# IFM_DuberFilter_ThroughHole_PCB.net
KiCad netlist of a schematic drawn in EAGLE
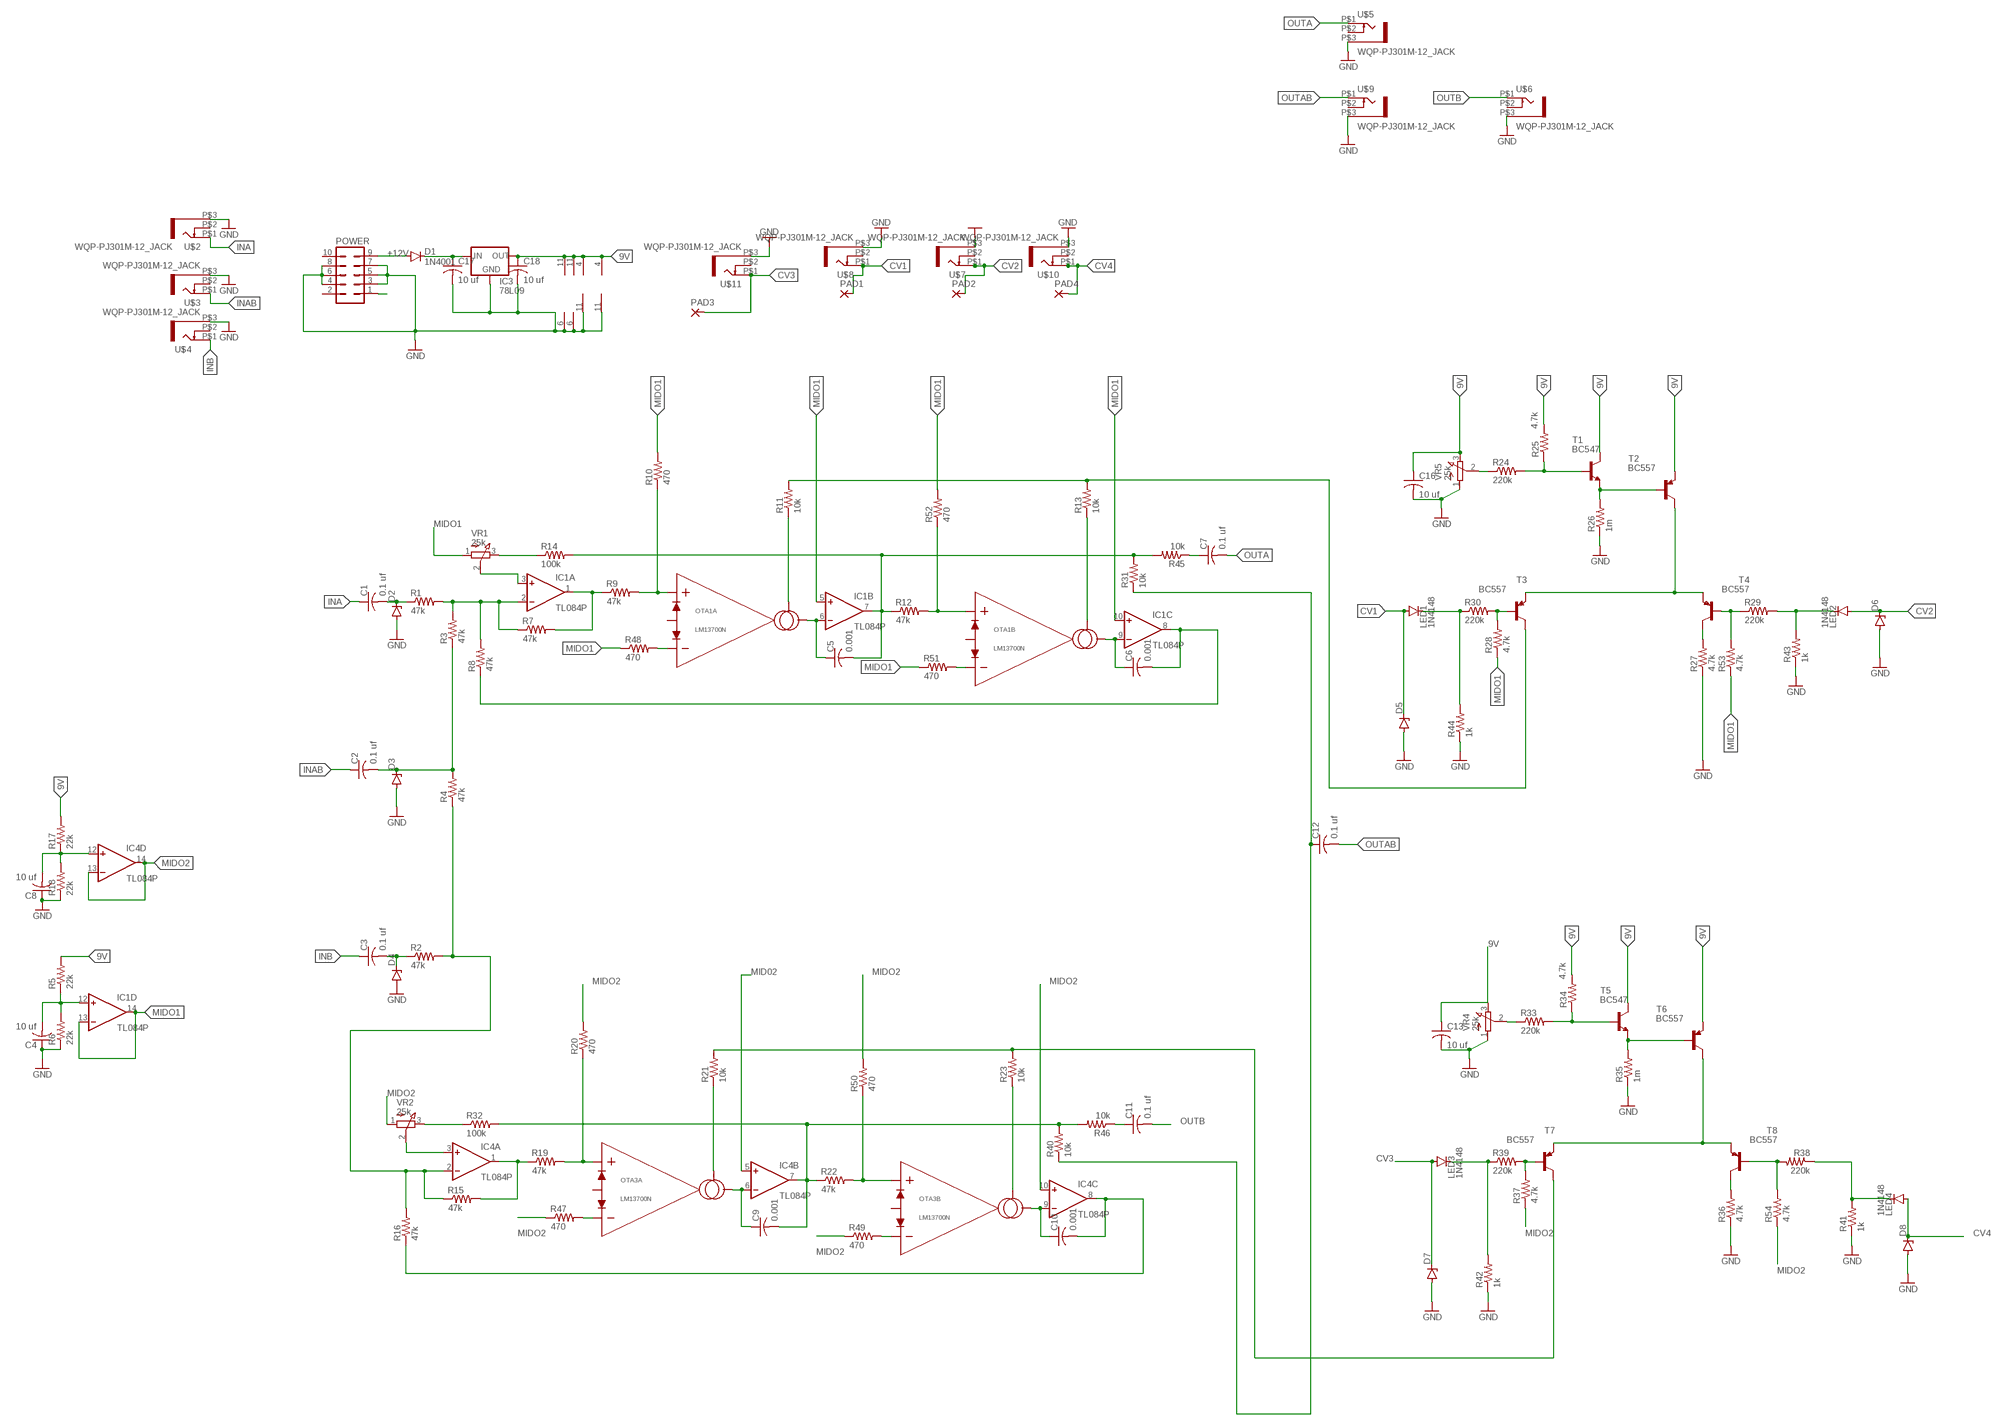
[diagram p0: schematic, sheet 1]

(export (version "E")
  (design (tool "Eeschema 10.0.6"))
  (components
    (comp (ref "C1")
      (value "0.1 uf")
      (footprint "eagle-import:C050-030X075")
      (libsource (lib "eagle-import") (part "C-US050-030X075"))
    )
    (comp (ref "C2")
      (value "0.1 uf")
      (footprint "eagle-import:C050-030X075")
      (libsource (lib "eagle-import") (part "C-US050-030X075"))
    )
    (comp (ref "C3")
      (value "0.1 uf")
      (footprint "eagle-import:C050-030X075")
      (libsource (lib "eagle-import") (part "C-US050-030X075"))
    )
    (comp (ref "C4")
      (value "10 uf")
      (footprint "eagle-import:C050-030X075")
      (libsource (lib "eagle-import") (part "C-US050-030X075"))
    )
    (comp (ref "C5")
      (value "0.001")
      (footprint "eagle-import:C050-030X075")
      (libsource (lib "eagle-import") (part "C-US050-030X075"))
    )
    (comp (ref "C6")
      (value "0.001")
      (footprint "eagle-import:C050-030X075")
      (libsource (lib "eagle-import") (part "C-US050-030X075"))
    )
    (comp (ref "C7")
      (value "0.1 uf")
      (footprint "eagle-import:C050-030X075")
      (libsource (lib "eagle-import") (part "C-US050-030X075"))
    )
    (comp (ref "C8")
      (value "10 uf")
      (footprint "eagle-import:C050-030X075")
      (libsource (lib "eagle-import") (part "C-US050-030X075"))
    )
    (comp (ref "C9")
      (value "0.001")
      (footprint "eagle-import:C050-030X075")
      (libsource (lib "eagle-import") (part "C-US050-030X075"))
    )
    (comp (ref "C10")
      (value "0.001")
      (footprint "eagle-import:C050-030X075")
      (libsource (lib "eagle-import") (part "C-US050-030X075"))
    )
    (comp (ref "C11")
      (value "0.1 uf")
      (footprint "eagle-import:C050-030X075")
      (libsource (lib "eagle-import") (part "C-US050-030X075"))
    )
    (comp (ref "C12")
      (value "0.1 uf")
      (footprint "eagle-import:C050-030X075")
      (libsource (lib "eagle-import") (part "C-US050-030X075"))
    )
    (comp (ref "C13")
      (value "10 uf")
      (footprint "eagle-import:C050-030X075")
      (libsource (lib "eagle-import") (part "C-US050-030X075"))
    )
    (comp (ref "C16")
      (value "10 uf")
      (footprint "eagle-import:C050-030X075")
      (libsource (lib "eagle-import") (part "C-US050-030X075"))
    )
    (comp (ref "C17")
      (value "10 uf")
      (footprint "eagle-import:C050-030X075")
      (libsource (lib "eagle-import") (part "C-US050-030X075"))
    )
    (comp (ref "C18")
      (value "10 uf")
      (footprint "eagle-import:C050-030X075")
      (libsource (lib "eagle-import") (part "C-US050-030X075"))
    )
    (comp (ref "D1")
      (value "1N4001")
      (footprint "eagle-import:DO41-10")
      (libsource (lib "eagle-import") (part "1N4004"))
    )
    (comp (ref "D2")
      (value "ZENER-DIODEDO34-7")
      (footprint "eagle-import:DO34Z7")
      (libsource (lib "eagle-import") (part "ZENER-DIODEDO34-7"))
    )
    (comp (ref "D3")
      (value "ZENER-DIODEDO34-7")
      (footprint "eagle-import:DO34Z7")
      (fields (field (name "SPICEPREFIX") "D"))
      (libsource (lib "eagle-import") (part "ZENER-DIODEDO34-7"))
    )
    (comp (ref "D4")
      (value "ZENER-DIODEDO34-7")
      (footprint "eagle-import:DO34Z7")
      (libsource (lib "eagle-import") (part "ZENER-DIODEDO34-7"))
    )
    (comp (ref "D5")
      (value "ZENER-DIODEDO34-7")
      (footprint "eagle-import:DO34Z7")
      (libsource (lib "eagle-import") (part "ZENER-DIODEDO34-7"))
    )
    (comp (ref "D6")
      (value "ZENER-DIODEDO34-7")
      (footprint "eagle-import:DO34Z7")
      (libsource (lib "eagle-import") (part "ZENER-DIODEDO34-7"))
    )
    (comp (ref "D7")
      (value "ZENER-DIODEDO34-7")
      (footprint "eagle-import:DO34Z7")
      (libsource (lib "eagle-import") (part "ZENER-DIODEDO34-7"))
    )
    (comp (ref "D8")
      (value "ZENER-DIODEDO34-7")
      (footprint "eagle-import:DO34Z7")
      (libsource (lib "eagle-import") (part "ZENER-DIODEDO34-7"))
    )
    (comp (ref "IC1")
      (value "TL084P")
      (footprint "eagle-import:DIL14")
      (libsource (lib "eagle-import") (part "TL084P"))
    )
    (comp (ref "IC3")
      (value "78L09")
      (footprint "eagle-import:78LXX")
      (libsource (lib "eagle-import") (part "78LXX"))
    )
    (comp (ref "IC4")
      (value "TL084P")
      (footprint "eagle-import:DIL14")
      (libsource (lib "eagle-import") (part "TL084P"))
    )
    (comp (ref "LED1")
      (value "1N4148")
      (footprint "eagle-import:DO35-7")
      (fields (field (name "SPICEPREFIX") "L"))
      (libsource (lib "eagle-import") (part "1N4148DO35-7"))
    )
    (comp (ref "LED2")
      (value "1N4148")
      (footprint "eagle-import:DO35-7")
      (libsource (lib "eagle-import") (part "1N4148DO35-7"))
    )
    (comp (ref "LED3")
      (value "1N4148")
      (footprint "eagle-import:DO35-7")
      (fields (field (name "SPICEPREFIX") "L"))
      (libsource (lib "eagle-import") (part "1N4148DO35-7"))
    )
    (comp (ref "LED4")
      (value "1N4148")
      (footprint "eagle-import:DO35-7")
      (libsource (lib "eagle-import") (part "1N4148DO35-7"))
    )
    (comp (ref "OTA1")
      (value "LM13700N")
      (footprint "eagle-import:DIP16")
      (libsource (lib "eagle-import") (part "LM13700N"))
    )
    (comp (ref "OTA3")
      (value "LM13700N")
      (footprint "eagle-import:DIP16")
      (libsource (lib "eagle-import") (part "LM13700N"))
    )
    (comp (ref "PAD1")
      (value "SMD2")
      (footprint "eagle-import:SMD1,27-2,54")
      (libsource (lib "eagle-import") (part "SMD2"))
    )
    (comp (ref "PAD2")
      (value "SMD2")
      (footprint "eagle-import:SMD1,27-2,54")
      (libsource (lib "eagle-import") (part "SMD2"))
    )
    (comp (ref "PAD3")
      (value "SMD2")
      (footprint "eagle-import:SMD1,27-2,54")
      (libsource (lib "eagle-import") (part "SMD2"))
    )
    (comp (ref "PAD4")
      (value "SMD2")
      (footprint "eagle-import:SMD1,27-2,54")
      (libsource (lib "eagle-import") (part "SMD2"))
    )
    (comp (ref "POWER")
      (value "10_PIN_HEADER")
      (footprint "eagle-import:MA05-2")
      (libsource (lib "eagle-import") (part "10_PIN_HEADER"))
    )
    (comp (ref "R1")
      (value "47k")
      (footprint "eagle-import:0204_7")
      (libsource (lib "eagle-import") (part "R-US_0204/7"))
    )
    (comp (ref "R2")
      (value "47k")
      (footprint "eagle-import:0204_7")
      (libsource (lib "eagle-import") (part "R-US_0204/7"))
    )
    (comp (ref "R3")
      (value "47k")
      (footprint "eagle-import:0204_7")
      (libsource (lib "eagle-import") (part "R-US_0204/7"))
    )
    (comp (ref "R4")
      (value "47k")
      (footprint "eagle-import:0204_7")
      (libsource (lib "eagle-import") (part "R-US_0204/7"))
    )
    (comp (ref "R5")
      (value "22k")
      (footprint "eagle-import:0204_7")
      (libsource (lib "eagle-import") (part "R-US_0204/7"))
    )
    (comp (ref "R6")
      (value "22k")
      (footprint "eagle-import:0204_7")
      (libsource (lib "eagle-import") (part "R-US_0204/7"))
    )
    (comp (ref "R7")
      (value "47k")
      (footprint "eagle-import:0204_7")
      (libsource (lib "eagle-import") (part "R-US_0204/7"))
    )
    (comp (ref "R8")
      (value "47k")
      (footprint "eagle-import:0204_7")
      (libsource (lib "eagle-import") (part "R-US_0204/7"))
    )
    (comp (ref "R9")
      (value "47k")
      (footprint "eagle-import:0204_7")
      (libsource (lib "eagle-import") (part "R-US_0204/7"))
    )
    (comp (ref "R10")
      (value "470")
      (footprint "eagle-import:0204_7")
      (libsource (lib "eagle-import") (part "R-US_0204/7"))
    )
    (comp (ref "R11")
      (value "10k")
      (footprint "eagle-import:0204_7")
      (libsource (lib "eagle-import") (part "R-US_0204/7"))
    )
    (comp (ref "R12")
      (value "47k")
      (footprint "eagle-import:0204_7")
      (libsource (lib "eagle-import") (part "R-US_0204/7"))
    )
    (comp (ref "R13")
      (value "10k")
      (footprint "eagle-import:0204_7")
      (libsource (lib "eagle-import") (part "R-US_0204/7"))
    )
    (comp (ref "R14")
      (value "100k")
      (footprint "eagle-import:0204_7")
      (libsource (lib "eagle-import") (part "R-US_0204/7"))
    )
    (comp (ref "R15")
      (value "47k")
      (footprint "eagle-import:0204_7")
      (libsource (lib "eagle-import") (part "R-US_0204/7"))
    )
    (comp (ref "R16")
      (value "47k")
      (footprint "eagle-import:0204_7")
      (libsource (lib "eagle-import") (part "R-US_0204/7"))
    )
    (comp (ref "R17")
      (value "22k")
      (footprint "eagle-import:0204_7")
      (libsource (lib "eagle-import") (part "R-US_0204/7"))
    )
    (comp (ref "R18")
      (value "22k")
      (footprint "eagle-import:0204_7")
      (libsource (lib "eagle-import") (part "R-US_0204/7"))
    )
    (comp (ref "R19")
      (value "47k")
      (footprint "eagle-import:0204_7")
      (libsource (lib "eagle-import") (part "R-US_0204/7"))
    )
    (comp (ref "R20")
      (value "470")
      (footprint "eagle-import:0204_7")
      (libsource (lib "eagle-import") (part "R-US_0204/7"))
    )
    (comp (ref "R21")
      (value "10k")
      (footprint "eagle-import:0204_7")
      (libsource (lib "eagle-import") (part "R-US_0204/7"))
    )
    (comp (ref "R22")
      (value "47k")
      (footprint "eagle-import:0204_7")
      (libsource (lib "eagle-import") (part "R-US_0204/7"))
    )
    (comp (ref "R23")
      (value "10k")
      (footprint "eagle-import:0204_7")
      (libsource (lib "eagle-import") (part "R-US_0204/7"))
    )
    (comp (ref "R24")
      (value "220k")
      (footprint "eagle-import:0204_7")
      (libsource (lib "eagle-import") (part "R-US_0204/7"))
    )
    (comp (ref "R25")
      (value "4.7k")
      (footprint "eagle-import:0204_7")
      (libsource (lib "eagle-import") (part "R-US_0204/7"))
    )
    (comp (ref "R26")
      (value "1m")
      (footprint "eagle-import:0204_7")
      (libsource (lib "eagle-import") (part "R-US_0204/7"))
    )
    (comp (ref "R27")
      (value "4.7k")
      (footprint "eagle-import:0204_7")
      (libsource (lib "eagle-import") (part "R-US_0204/7"))
    )
    (comp (ref "R28")
      (value "4.7k")
      (footprint "eagle-import:0204_7")
      (libsource (lib "eagle-import") (part "R-US_0204/7"))
    )
    (comp (ref "R29")
      (value "220k")
      (footprint "eagle-import:0204_7")
      (libsource (lib "eagle-import") (part "R-US_0204/7"))
    )
    (comp (ref "R30")
      (value "220k")
      (footprint "eagle-import:0204_7")
      (libsource (lib "eagle-import") (part "R-US_0204/7"))
    )
    (comp (ref "R31")
      (value "10k")
      (footprint "eagle-import:0204_7")
      (libsource (lib "eagle-import") (part "R-US_0204/7"))
    )
    (comp (ref "R32")
      (value "100k")
      (footprint "eagle-import:0204_7")
      (libsource (lib "eagle-import") (part "R-US_0204/7"))
    )
    (comp (ref "R33")
      (value "220k")
      (footprint "eagle-import:0204_7")
      (libsource (lib "eagle-import") (part "R-US_0204/7"))
    )
    (comp (ref "R34")
      (value "4.7k")
      (footprint "eagle-import:0204_7")
      (libsource (lib "eagle-import") (part "R-US_0204/7"))
    )
    (comp (ref "R35")
      (value "1m")
      (footprint "eagle-import:0204_7")
      (libsource (lib "eagle-import") (part "R-US_0204/7"))
    )
    (comp (ref "R36")
      (value "4.7k")
      (footprint "eagle-import:0204_7")
      (libsource (lib "eagle-import") (part "R-US_0204/7"))
    )
    (comp (ref "R37")
      (value "4.7k")
      (footprint "eagle-import:0204_7")
      (libsource (lib "eagle-import") (part "R-US_0204/7"))
    )
    (comp (ref "R38")
      (value "220k")
      (footprint "eagle-import:0204_7")
      (libsource (lib "eagle-import") (part "R-US_0204/7"))
    )
    (comp (ref "R39")
      (value "220k")
      (footprint "eagle-import:0204_7")
      (libsource (lib "eagle-import") (part "R-US_0204/7"))
    )
    (comp (ref "R40")
      (value "10k")
      (footprint "eagle-import:0204_7")
      (libsource (lib "eagle-import") (part "R-US_0204/7"))
    )
    (comp (ref "R41")
      (value "1k")
      (footprint "eagle-import:0204_7")
      (libsource (lib "eagle-import") (part "R-US_0204/7"))
    )
    (comp (ref "R42")
      (value "1k")
      (footprint "eagle-import:0204_7")
      (libsource (lib "eagle-import") (part "R-US_0204/7"))
    )
    (comp (ref "R43")
      (value "1k")
      (footprint "eagle-import:0204_7")
      (libsource (lib "eagle-import") (part "R-US_0204/7"))
    )
    (comp (ref "R44")
      (value "1k")
      (footprint "eagle-import:0204_7")
      (libsource (lib "eagle-import") (part "R-US_0204/7"))
    )
    (comp (ref "R45")
      (value "10k")
      (footprint "eagle-import:0204_7")
      (libsource (lib "eagle-import") (part "R-US_0204/7"))
    )
    (comp (ref "R46")
      (value "10k")
      (footprint "eagle-import:0204_7")
      (libsource (lib "eagle-import") (part "R-US_0204/7"))
    )
    (comp (ref "R47")
      (value "470")
      (footprint "eagle-import:0204_7")
      (libsource (lib "eagle-import") (part "R-US_0204/7"))
    )
    (comp (ref "R48")
      (value "470")
      (footprint "eagle-import:0204_7")
      (libsource (lib "eagle-import") (part "R-US_0204/7"))
    )
    (comp (ref "R49")
      (value "470")
      (footprint "eagle-import:0204_7")
      (libsource (lib "eagle-import") (part "R-US_0204/7"))
    )
    (comp (ref "R50")
      (value "470")
      (footprint "eagle-import:0204_7")
      (libsource (lib "eagle-import") (part "R-US_0204/7"))
    )
    (comp (ref "R51")
      (value "470")
      (footprint "eagle-import:0204_7")
      (libsource (lib "eagle-import") (part "R-US_0204/7"))
    )
    (comp (ref "R52")
      (value "470")
      (footprint "eagle-import:0204_7")
      (libsource (lib "eagle-import") (part "R-US_0204/7"))
    )
    (comp (ref "R53")
      (value "4.7k")
      (footprint "eagle-import:0204_7")
      (libsource (lib "eagle-import") (part "R-US_0204/7"))
    )
    (comp (ref "R54")
      (value "4.7k")
      (footprint "eagle-import:0204_7")
      (libsource (lib "eagle-import") (part "R-US_0204/7"))
    )
    (comp (ref "T1")
      (value "BC547")
      (footprint "eagle-import:TO92")
      (libsource (lib "eagle-import") (part "BC547"))
    )
    (comp (ref "T2")
      (value "BC557")
      (footprint "eagle-import:TO92-EBC")
      (libsource (lib "eagle-import") (part "-PNP-TO92-EBCBC557A"))
    )
    (comp (ref "T3")
      (value "BC557")
      (footprint "eagle-import:TO92-EBC")
      (libsource (lib "eagle-import") (part "-PNP-TO92-EBCBC557A"))
    )
    (comp (ref "T4")
      (value "BC557")
      (footprint "eagle-import:TO92-EBC")
      (libsource (lib "eagle-import") (part "-PNP-TO92-EBCBC557A"))
    )
    (comp (ref "T5")
      (value "BC547")
      (footprint "eagle-import:TO92")
      (libsource (lib "eagle-import") (part "BC547"))
    )
    (comp (ref "T6")
      (value "BC557")
      (footprint "eagle-import:TO92-EBC")
      (libsource (lib "eagle-import") (part "-PNP-TO92-EBCBC557A"))
    )
    (comp (ref "T7")
      (value "BC557")
      (footprint "eagle-import:TO92-EBC")
      (libsource (lib "eagle-import") (part "-PNP-TO92-EBCBC557A"))
    )
    (comp (ref "T8")
      (value "BC557")
      (footprint "eagle-import:TO92-EBC")
      (libsource (lib "eagle-import") (part "-PNP-TO92-EBCBC557A"))
    )
    (comp (ref "U$2")
      (value "WQP-PJ301M-12_JACK")
      (footprint "eagle-import:WQP-PJ301M-12_JACK")
      (libsource (lib "eagle-import") (part "WQP-PJ301M-12_JACK"))
    )
    (comp (ref "U$3")
      (value "WQP-PJ301M-12_JACK")
      (footprint "eagle-import:WQP-PJ301M-12_JACK")
      (libsource (lib "eagle-import") (part "WQP-PJ301M-12_JACK"))
    )
    (comp (ref "U$4")
      (value "WQP-PJ301M-12_JACK")
      (footprint "eagle-import:WQP-PJ301M-12_JACK")
      (libsource (lib "eagle-import") (part "WQP-PJ301M-12_JACK"))
    )
    (comp (ref "U$5")
      (value "WQP-PJ301M-12_JACK")
      (footprint "eagle-import:WQP-PJ301M-12_JACK")
      (libsource (lib "eagle-import") (part "WQP-PJ301M-12_JACK"))
    )
    (comp (ref "U$6")
      (value "WQP-PJ301M-12_JACK")
      (footprint "eagle-import:WQP-PJ301M-12_JACK")
      (libsource (lib "eagle-import") (part "WQP-PJ301M-12_JACK"))
    )
    (comp (ref "U$7")
      (value "WQP-PJ301M-12_JACK")
      (footprint "eagle-import:WQP-PJ301M-12_JACK")
      (libsource (lib "eagle-import") (part "WQP-PJ301M-12_JACK"))
    )
    (comp (ref "U$8")
      (value "WQP-PJ301M-12_JACK")
      (footprint "eagle-import:WQP-PJ301M-12_JACK")
      (libsource (lib "eagle-import") (part "WQP-PJ301M-12_JACK"))
    )
    (comp (ref "U$9")
      (value "WQP-PJ301M-12_JACK")
      (footprint "eagle-import:WQP-PJ301M-12_JACK")
      (libsource (lib "eagle-import") (part "WQP-PJ301M-12_JACK"))
    )
    (comp (ref "U$10")
      (value "WQP-PJ301M-12_JACK")
      (footprint "eagle-import:WQP-PJ301M-12_JACK")
      (libsource (lib "eagle-import") (part "WQP-PJ301M-12_JACK"))
    )
    (comp (ref "U$11")
      (value "WQP-PJ301M-12_JACK")
      (footprint "eagle-import:WQP-PJ301M-12_JACK")
      (libsource (lib "eagle-import") (part "WQP-PJ301M-12_JACK"))
    )
    (comp (ref "VR1")
      (value "25k")
      (footprint "eagle-import:EVUFXL")
      (libsource (lib "eagle-import") (part "EVULF3"))
    )
    (comp (ref "VR2")
      (value "25k")
      (footprint "eagle-import:EVUFXL")
      (libsource (lib "eagle-import") (part "EVULF3"))
    )
    (comp (ref "VR4")
      (value "25k")
      (footprint "eagle-import:EVUFXL")
      (libsource (lib "eagle-import") (part "EVULF3"))
    )
    (comp (ref "VR5")
      (value "25k")
      (footprint "eagle-import:EVUFXL")
      (libsource (lib "eagle-import") (part "EVULF3"))
    )
  )
  (nets
    (net (code "1") (name "/+12V") (class "Default")
      (node (ref "C17") (pin "1") (pinfunction "1_1") (pintype "passive"))
      (node (ref "D1") (pin "C") (pinfunction "C_C") (pintype "passive"))
      (node (ref "IC3") (pin "IN") (pinfunction "IN_IN") (pintype "input"))
    )
    (net (code "2") (name "/MID02") (class "Default")
      (node (ref "IC4") (pin "5") (pinfunction "+IN_5") (pintype "input"))
    )
    (net (code "3") (name "9V") (class "Default")
      (node (ref "C13") (pin "1") (pinfunction "1_1") (pintype "passive"))
      (node (ref "C16") (pin "1") (pinfunction "1_1") (pintype "passive"))
      (node (ref "C18") (pin "1") (pinfunction "1_1") (pintype "passive"))
      (node (ref "IC1") (pin "4") (pinfunction "V+_4") (pintype "power_in"))
      (node (ref "IC3") (pin "OUT") (pinfunction "OUT_OUT") (pintype "passive"))
      (node (ref "IC4") (pin "4") (pinfunction "V+_4") (pintype "power_in"))
      (node (ref "OTA1") (pin "11") (pinfunction "VCC_11") (pintype "power_in"))
      (node (ref "OTA3") (pin "11") (pinfunction "VCC_11") (pintype "power_in"))
      (node (ref "R17") (pin "2") (pinfunction "2_2") (pintype "passive"))
      (node (ref "R25") (pin "2") (pinfunction "2_2") (pintype "passive"))
      (node (ref "R34") (pin "2") (pinfunction "2_2") (pintype "passive"))
      (node (ref "R5") (pin "2") (pinfunction "2_2") (pintype "passive"))
      (node (ref "T1") (pin "3") (pinfunction "C_3") (pintype "passive"))
      (node (ref "T2") (pin "E") (pinfunction "E_E") (pintype "passive"))
      (node (ref "T5") (pin "3") (pinfunction "C_3") (pintype "passive"))
      (node (ref "T6") (pin "E") (pinfunction "E_E") (pintype "passive"))
      (node (ref "VR4") (pin "3") (pinfunction "E_3") (pintype "passive"))
      (node (ref "VR5") (pin "3") (pinfunction "E_3") (pintype "passive"))
    )
    (net (code "4") (name "CV1") (class "Default")
      (node (ref "D5") (pin "C") (pinfunction "C_C") (pintype "passive"))
      (node (ref "LED1") (pin "A") (pinfunction "A_A") (pintype "passive"))
      (node (ref "PAD1") (pin "1") (pinfunction "P_1") (pintype "passive"))
      (node (ref "U$8") (pin "P$1") (pinfunction "2_P$1") (pintype "passive"))
    )
    (net (code "5") (name "CV2") (class "Default")
      (node (ref "D6") (pin "C") (pinfunction "C_C") (pintype "passive"))
      (node (ref "LED2") (pin "A") (pinfunction "A_A") (pintype "passive"))
      (node (ref "PAD2") (pin "1") (pinfunction "P_1") (pintype "passive"))
      (node (ref "U$7") (pin "P$1") (pinfunction "2_P$1") (pintype "passive"))
    )
    (net (code "6") (name "CV3") (class "Default")
      (node (ref "D7") (pin "C") (pinfunction "C_C") (pintype "passive"))
      (node (ref "LED3") (pin "A") (pinfunction "A_A") (pintype "passive"))
      (node (ref "PAD3") (pin "1") (pinfunction "P_1") (pintype "passive"))
      (node (ref "U$11") (pin "P$1") (pinfunction "2_P$1") (pintype "passive"))
    )
    (net (code "7") (name "CV4") (class "Default")
      (node (ref "D8") (pin "C") (pinfunction "C_C") (pintype "passive"))
      (node (ref "LED4") (pin "A") (pinfunction "A_A") (pintype "passive"))
      (node (ref "PAD4") (pin "1") (pinfunction "P_1") (pintype "passive"))
      (node (ref "U$10") (pin "P$1") (pinfunction "2_P$1") (pintype "passive"))
    )
    (net (code "8") (name "GND") (class "Default")
      (node (ref "C13") (pin "2") (pinfunction "2_2") (pintype "passive"))
      (node (ref "C16") (pin "2") (pinfunction "2_2") (pintype "passive"))
      (node (ref "C17") (pin "2") (pinfunction "2_2") (pintype "passive"))
      (node (ref "C18") (pin "2") (pinfunction "2_2") (pintype "passive"))
      (node (ref "C4") (pin "1") (pinfunction "1_1") (pintype "passive"))
      (node (ref "C8") (pin "1") (pinfunction "1_1") (pintype "passive"))
      (node (ref "D2") (pin "A") (pinfunction "A_A") (pintype "passive"))
      (node (ref "D3") (pin "A") (pinfunction "A_A") (pintype "passive"))
      (node (ref "D4") (pin "A") (pinfunction "A_A") (pintype "passive"))
      (node (ref "D5") (pin "A") (pinfunction "A_A") (pintype "passive"))
      (node (ref "D6") (pin "A") (pinfunction "A_A") (pintype "passive"))
      (node (ref "D7") (pin "A") (pinfunction "A_A") (pintype "passive"))
      (node (ref "D8") (pin "A") (pinfunction "A_A") (pintype "passive"))
      (node (ref "IC1") (pin "11") (pinfunction "V-_11") (pintype "power_in"))
      (node (ref "IC3") (pin "GND") (pinfunction "GND_GND") (pintype "input"))
      (node (ref "IC4") (pin "11") (pinfunction "V-_11") (pintype "power_in"))
      (node (ref "OTA1") (pin "6") (pinfunction "VEE_6") (pintype "power_in"))
      (node (ref "OTA3") (pin "6") (pinfunction "VEE_6") (pintype "power_in"))
      (node (ref "POWER") (pin "3") (pinfunction "3_3") (pintype "passive"))
      (node (ref "POWER") (pin "4") (pinfunction "4_4") (pintype "passive"))
      (node (ref "POWER") (pin "5") (pinfunction "5_5") (pintype "passive"))
      (node (ref "POWER") (pin "6") (pinfunction "6_6") (pintype "passive"))
      (node (ref "POWER") (pin "7") (pinfunction "7_7") (pintype "passive"))
      (node (ref "POWER") (pin "8") (pinfunction "8_8") (pintype "passive"))
      (node (ref "R18") (pin "1") (pinfunction "1_1") (pintype "passive"))
      (node (ref "R26") (pin "1") (pinfunction "1_1") (pintype "passive"))
      (node (ref "R27") (pin "1") (pinfunction "1_1") (pintype "passive"))
      (node (ref "R35") (pin "1") (pinfunction "1_1") (pintype "passive"))
      (node (ref "R36") (pin "1") (pinfunction "1_1") (pintype "passive"))
      (node (ref "R41") (pin "1") (pinfunction "1_1") (pintype "passive"))
      (node (ref "R42") (pin "1") (pinfunction "1_1") (pintype "passive"))
      (node (ref "R43") (pin "1") (pinfunction "1_1") (pintype "passive"))
      (node (ref "R44") (pin "1") (pinfunction "1_1") (pintype "passive"))
      (node (ref "R6") (pin "1") (pinfunction "1_1") (pintype "passive"))
      (node (ref "U$10") (pin "P$3") (pinfunction "1_P$3") (pintype "passive"))
      (node (ref "U$11") (pin "P$3") (pinfunction "1_P$3") (pintype "passive"))
      (node (ref "U$2") (pin "P$3") (pinfunction "1_P$3") (pintype "passive"))
      (node (ref "U$3") (pin "P$3") (pinfunction "1_P$3") (pintype "passive"))
      (node (ref "U$4") (pin "P$3") (pinfunction "1_P$3") (pintype "passive"))
      (node (ref "U$5") (pin "P$3") (pinfunction "1_P$3") (pintype "passive"))
      (node (ref "U$6") (pin "P$3") (pinfunction "1_P$3") (pintype "passive"))
      (node (ref "U$7") (pin "P$3") (pinfunction "1_P$3") (pintype "passive"))
      (node (ref "U$8") (pin "P$3") (pinfunction "1_P$3") (pintype "passive"))
      (node (ref "U$9") (pin "P$3") (pinfunction "1_P$3") (pintype "passive"))
      (node (ref "VR4") (pin "1") (pinfunction "A_1") (pintype "passive"))
      (node (ref "VR5") (pin "1") (pinfunction "A_1") (pintype "passive"))
    )
    (net (code "9") (name "INA") (class "Default")
      (node (ref "C1") (pin "1") (pinfunction "1_1") (pintype "passive"))
      (node (ref "U$2") (pin "P$1") (pinfunction "2_P$1") (pintype "passive"))
    )
    (net (code "10") (name "INAB") (class "Default")
      (node (ref "C2") (pin "1") (pinfunction "1_1") (pintype "passive"))
      (node (ref "U$3") (pin "P$1") (pinfunction "2_P$1") (pintype "passive"))
    )
    (net (code "11") (name "INB") (class "Default")
      (node (ref "C3") (pin "1") (pinfunction "1_1") (pintype "passive"))
      (node (ref "U$4") (pin "P$1") (pinfunction "2_P$1") (pintype "passive"))
    )
    (net (code "12") (name "MIDO1") (class "Default")
      (node (ref "IC1") (pin "10") (pinfunction "+IN_10") (pintype "input"))
      (node (ref "IC1") (pin "13") (pinfunction "-IN_13") (pintype "input"))
      (node (ref "IC1") (pin "14") (pinfunction "OUT_14") (pintype "output"))
      (node (ref "IC1") (pin "5") (pinfunction "+IN_5") (pintype "input"))
      (node (ref "R10") (pin "2") (pinfunction "2_2") (pintype "passive"))
      (node (ref "R28") (pin "1") (pinfunction "1_1") (pintype "passive"))
      (node (ref "R48") (pin "1") (pinfunction "1_1") (pintype "passive"))
      (node (ref "R51") (pin "1") (pinfunction "1_1") (pintype "passive"))
      (node (ref "R52") (pin "2") (pinfunction "2_2") (pintype "passive"))
      (node (ref "R53") (pin "1") (pinfunction "1_1") (pintype "passive"))
      (node (ref "VR1") (pin "1") (pinfunction "A_1") (pintype "passive"))
    )
    (net (code "13") (name "MIDO2") (class "Default")
      (node (ref "IC4") (pin "10") (pinfunction "+IN_10") (pintype "input"))
      (node (ref "IC4") (pin "13") (pinfunction "-IN_13") (pintype "input"))
      (node (ref "IC4") (pin "14") (pinfunction "OUT_14") (pintype "output"))
      (node (ref "R20") (pin "2") (pinfunction "2_2") (pintype "passive"))
      (node (ref "R37") (pin "1") (pinfunction "1_1") (pintype "passive"))
      (node (ref "R47") (pin "1") (pinfunction "1_1") (pintype "passive"))
      (node (ref "R49") (pin "1") (pinfunction "1_1") (pintype "passive"))
      (node (ref "R50") (pin "2") (pinfunction "2_2") (pintype "passive"))
      (node (ref "R54") (pin "1") (pinfunction "1_1") (pintype "passive"))
      (node (ref "VR2") (pin "1") (pinfunction "A_1") (pintype "passive"))
    )
    (net (code "14") (name "Net-(C1-Pad2)") (class "Default")
      (node (ref "C1") (pin "2") (pinfunction "2_2") (pintype "passive"))
      (node (ref "D2") (pin "C") (pinfunction "C_C") (pintype "passive"))
      (node (ref "R1") (pin "1") (pinfunction "1_1") (pintype "passive"))
    )
    (net (code "15") (name "Net-(C2-Pad2)") (class "Default")
      (node (ref "C2") (pin "2") (pinfunction "2_2") (pintype "passive"))
      (node (ref "D3") (pin "C") (pinfunction "C_C") (pintype "passive"))
      (node (ref "R3") (pin "1") (pinfunction "1_1") (pintype "passive"))
      (node (ref "R4") (pin "2") (pinfunction "2_2") (pintype "passive"))
    )
    (net (code "16") (name "Net-(C3-Pad2)") (class "Default")
      (node (ref "C3") (pin "2") (pinfunction "2_2") (pintype "passive"))
      (node (ref "D4") (pin "C") (pinfunction "C_C") (pintype "passive"))
      (node (ref "R2") (pin "1") (pinfunction "1_1") (pintype "passive"))
    )
    (net (code "17") (name "Net-(C7-Pad1)") (class "Default")
      (node (ref "C7") (pin "1") (pinfunction "1_1") (pintype "passive"))
      (node (ref "R45") (pin "1") (pinfunction "1_1") (pintype "passive"))
    )
    (net (code "18") (name "Net-(C11-Pad1)") (class "Default")
      (node (ref "C11") (pin "1") (pinfunction "1_1") (pintype "passive"))
      (node (ref "R46") (pin "1") (pinfunction "1_1") (pintype "passive"))
    )
    (net (code "19") (name "Net-(C12-Pad1)") (class "Default")
      (node (ref "C12") (pin "1") (pinfunction "1_1") (pintype "passive"))
      (node (ref "R31") (pin "1") (pinfunction "1_1") (pintype "passive"))
      (node (ref "R40") (pin "1") (pinfunction "1_1") (pintype "passive"))
    )
    (net (code "20") (name "Net-(D1-PadA)") (class "Default")
      (node (ref "D1") (pin "A") (pinfunction "A_A") (pintype "passive"))
      (node (ref "POWER") (pin "9") (pinfunction "9_9") (pintype "passive"))
    )
    (net (code "21") (name "Net-(IC1A-+IN)") (class "Default")
      (node (ref "IC1") (pin "3") (pinfunction "+IN_3") (pintype "input"))
      (node (ref "VR1") (pin "2") (pinfunction "S_2") (pintype "passive"))
    )
    (net (code "22") (name "Net-(IC1A--IN)") (class "Default")
      (node (ref "IC1") (pin "2") (pinfunction "-IN_2") (pintype "input"))
      (node (ref "R1") (pin "2") (pinfunction "2_2") (pintype "passive"))
      (node (ref "R3") (pin "2") (pinfunction "2_2") (pintype "passive"))
      (node (ref "R7") (pin "1") (pinfunction "1_1") (pintype "passive"))
      (node (ref "R8") (pin "2") (pinfunction "2_2") (pintype "passive"))
    )
    (net (code "23") (name "Net-(IC1A-OUT)") (class "Default")
      (node (ref "IC1") (pin "1") (pinfunction "OUT_1") (pintype "output"))
      (node (ref "R7") (pin "2") (pinfunction "2_2") (pintype "passive"))
      (node (ref "R9") (pin "1") (pinfunction "1_1") (pintype "passive"))
    )
    (net (code "24") (name "Net-(IC1B--IN)") (class "Default")
      (node (ref "C5") (pin "1") (pinfunction "1_1") (pintype "passive"))
      (node (ref "IC1") (pin "6") (pinfunction "-IN_6") (pintype "input"))
      (node (ref "OTA1") (pin "5") (pinfunction "IOUT_5") (pintype "output"))
    )
    (net (code "25") (name "Net-(IC1B-OUT)") (class "Default")
      (node (ref "C5") (pin "2") (pinfunction "2_2") (pintype "passive"))
      (node (ref "IC1") (pin "7") (pinfunction "OUT_7") (pintype "output"))
      (node (ref "R12") (pin "1") (pinfunction "1_1") (pintype "passive"))
      (node (ref "R14") (pin "2") (pinfunction "2_2") (pintype "passive"))
      (node (ref "R31") (pin "2") (pinfunction "2_2") (pintype "passive"))
      (node (ref "R45") (pin "2") (pinfunction "2_2") (pintype "passive"))
    )
    (net (code "26") (name "Net-(IC1C--IN)") (class "Default")
      (node (ref "C6") (pin "1") (pinfunction "1_1") (pintype "passive"))
      (node (ref "IC1") (pin "9") (pinfunction "-IN_9") (pintype "input"))
      (node (ref "OTA1") (pin "12") (pinfunction "IOUT_12") (pintype "output"))
    )
    (net (code "27") (name "Net-(IC1C-OUT)") (class "Default")
      (node (ref "C6") (pin "2") (pinfunction "2_2") (pintype "passive"))
      (node (ref "IC1") (pin "8") (pinfunction "OUT_8") (pintype "output"))
      (node (ref "R8") (pin "1") (pinfunction "1_1") (pintype "passive"))
    )
    (net (code "28") (name "Net-(IC1D-+IN)") (class "Default")
      (node (ref "C4") (pin "2") (pinfunction "2_2") (pintype "passive"))
      (node (ref "IC1") (pin "12") (pinfunction "+IN_12") (pintype "input"))
      (node (ref "R5") (pin "1") (pinfunction "1_1") (pintype "passive"))
      (node (ref "R6") (pin "2") (pinfunction "2_2") (pintype "passive"))
    )
    (net (code "29") (name "Net-(IC4A-+IN)") (class "Default")
      (node (ref "IC4") (pin "3") (pinfunction "+IN_3") (pintype "input"))
      (node (ref "VR2") (pin "2") (pinfunction "S_2") (pintype "passive"))
    )
    (net (code "30") (name "Net-(IC4A--IN)") (class "Default")
      (node (ref "IC4") (pin "2") (pinfunction "-IN_2") (pintype "input"))
      (node (ref "R15") (pin "1") (pinfunction "1_1") (pintype "passive"))
      (node (ref "R16") (pin "2") (pinfunction "2_2") (pintype "passive"))
      (node (ref "R2") (pin "2") (pinfunction "2_2") (pintype "passive"))
      (node (ref "R4") (pin "1") (pinfunction "1_1") (pintype "passive"))
    )
    (net (code "31") (name "Net-(IC4A-OUT)") (class "Default")
      (node (ref "IC4") (pin "1") (pinfunction "OUT_1") (pintype "output"))
      (node (ref "R15") (pin "2") (pinfunction "2_2") (pintype "passive"))
      (node (ref "R19") (pin "1") (pinfunction "1_1") (pintype "passive"))
    )
    (net (code "32") (name "Net-(IC4B--IN)") (class "Default")
      (node (ref "C9") (pin "1") (pinfunction "1_1") (pintype "passive"))
      (node (ref "IC4") (pin "6") (pinfunction "-IN_6") (pintype "input"))
      (node (ref "OTA3") (pin "5") (pinfunction "IOUT_5") (pintype "output"))
    )
    (net (code "33") (name "Net-(IC4B-OUT)") (class "Default")
      (node (ref "C9") (pin "2") (pinfunction "2_2") (pintype "passive"))
      (node (ref "IC4") (pin "7") (pinfunction "OUT_7") (pintype "output"))
      (node (ref "R22") (pin "1") (pinfunction "1_1") (pintype "passive"))
      (node (ref "R32") (pin "2") (pinfunction "2_2") (pintype "passive"))
      (node (ref "R40") (pin "2") (pinfunction "2_2") (pintype "passive"))
      (node (ref "R46") (pin "2") (pinfunction "2_2") (pintype "passive"))
    )
    (net (code "34") (name "Net-(IC4C--IN)") (class "Default")
      (node (ref "C10") (pin "1") (pinfunction "1_1") (pintype "passive"))
      (node (ref "IC4") (pin "9") (pinfunction "-IN_9") (pintype "input"))
      (node (ref "OTA3") (pin "12") (pinfunction "IOUT_12") (pintype "output"))
    )
    (net (code "35") (name "Net-(IC4C-OUT)") (class "Default")
      (node (ref "C10") (pin "2") (pinfunction "2_2") (pintype "passive"))
      (node (ref "IC4") (pin "8") (pinfunction "OUT_8") (pintype "output"))
      (node (ref "R16") (pin "1") (pinfunction "1_1") (pintype "passive"))
    )
    (net (code "36") (name "Net-(IC4D-+IN)") (class "Default")
      (node (ref "C8") (pin "2") (pinfunction "2_2") (pintype "passive"))
      (node (ref "IC4") (pin "12") (pinfunction "+IN_12") (pintype "input"))
      (node (ref "R17") (pin "1") (pinfunction "1_1") (pintype "passive"))
      (node (ref "R18") (pin "2") (pinfunction "2_2") (pintype "passive"))
    )
    (net (code "37") (name "Net-(LED1-PadC)") (class "Default")
      (node (ref "LED1") (pin "C") (pinfunction "C_C") (pintype "passive"))
      (node (ref "R30") (pin "1") (pinfunction "1_1") (pintype "passive"))
      (node (ref "R44") (pin "2") (pinfunction "2_2") (pintype "passive"))
    )
    (net (code "38") (name "Net-(LED2-PadC)") (class "Default")
      (node (ref "LED2") (pin "C") (pinfunction "C_C") (pintype "passive"))
      (node (ref "R29") (pin "2") (pinfunction "2_2") (pintype "passive"))
      (node (ref "R43") (pin "2") (pinfunction "2_2") (pintype "passive"))
    )
    (net (code "39") (name "Net-(LED3-PadC)") (class "Default")
      (node (ref "LED3") (pin "C") (pinfunction "C_C") (pintype "passive"))
      (node (ref "R39") (pin "1") (pinfunction "1_1") (pintype "passive"))
      (node (ref "R42") (pin "2") (pinfunction "2_2") (pintype "passive"))
    )
    (net (code "40") (name "Net-(LED4-PadC)") (class "Default")
      (node (ref "LED4") (pin "C") (pinfunction "C_C") (pintype "passive"))
      (node (ref "R38") (pin "1") (pinfunction "1_1") (pintype "passive"))
      (node (ref "R41") (pin "2") (pinfunction "2_2") (pintype "passive"))
    )
    (net (code "41") (name "Net-(OTA1A-IABC)") (class "Default")
      (node (ref "OTA1") (pin "1") (pinfunction "IABC_1") (pintype "input"))
      (node (ref "R11") (pin "1") (pinfunction "1_1") (pintype "passive"))
    )
    (net (code "42") (name "Net-(OTA1A-IN+)") (class "Default")
      (node (ref "OTA1") (pin "3") (pinfunction "IN+_3") (pintype "input"))
      (node (ref "R10") (pin "1") (pinfunction "1_1") (pintype "passive"))
      (node (ref "R9") (pin "2") (pinfunction "2_2") (pintype "passive"))
    )
    (net (code "43") (name "Net-(OTA1A-IN-)") (class "Default")
      (node (ref "OTA1") (pin "4") (pinfunction "IN-_4") (pintype "input"))
      (node (ref "R48") (pin "2") (pinfunction "2_2") (pintype "passive"))
    )
    (net (code "44") (name "Net-(OTA1B-IABC)") (class "Default")
      (node (ref "OTA1") (pin "16") (pinfunction "IABC_16") (pintype "input"))
      (node (ref "R13") (pin "1") (pinfunction "1_1") (pintype "passive"))
    )
    (net (code "45") (name "Net-(OTA1B-IN+)") (class "Default")
      (node (ref "OTA1") (pin "14") (pinfunction "IN+_14") (pintype "input"))
      (node (ref "R12") (pin "2") (pinfunction "2_2") (pintype "passive"))
      (node (ref "R52") (pin "1") (pinfunction "1_1") (pintype "passive"))
    )
    (net (code "46") (name "Net-(OTA1B-IN-)") (class "Default")
      (node (ref "OTA1") (pin "13") (pinfunction "IN-_13") (pintype "input"))
      (node (ref "R51") (pin "2") (pinfunction "2_2") (pintype "passive"))
    )
    (net (code "47") (name "Net-(OTA3A-IABC)") (class "Default")
      (node (ref "OTA3") (pin "1") (pinfunction "IABC_1") (pintype "input"))
      (node (ref "R21") (pin "1") (pinfunction "1_1") (pintype "passive"))
    )
    (net (code "48") (name "Net-(OTA3A-IN+)") (class "Default")
      (node (ref "OTA3") (pin "3") (pinfunction "IN+_3") (pintype "input"))
      (node (ref "R19") (pin "2") (pinfunction "2_2") (pintype "passive"))
      (node (ref "R20") (pin "1") (pinfunction "1_1") (pintype "passive"))
    )
    (net (code "49") (name "Net-(OTA3A-IN-)") (class "Default")
      (node (ref "OTA3") (pin "4") (pinfunction "IN-_4") (pintype "input"))
      (node (ref "R47") (pin "2") (pinfunction "2_2") (pintype "passive"))
    )
    (net (code "50") (name "Net-(OTA3B-IABC)") (class "Default")
      (node (ref "OTA3") (pin "16") (pinfunction "IABC_16") (pintype "input"))
      (node (ref "R23") (pin "1") (pinfunction "1_1") (pintype "passive"))
    )
    (net (code "51") (name "Net-(OTA3B-IN+)") (class "Default")
      (node (ref "OTA3") (pin "14") (pinfunction "IN+_14") (pintype "input"))
      (node (ref "R22") (pin "2") (pinfunction "2_2") (pintype "passive"))
      (node (ref "R50") (pin "1") (pinfunction "1_1") (pintype "passive"))
    )
    (net (code "52") (name "Net-(OTA3B-IN-)") (class "Default")
      (node (ref "OTA3") (pin "13") (pinfunction "IN-_13") (pintype "input"))
      (node (ref "R49") (pin "2") (pinfunction "2_2") (pintype "passive"))
    )
    (net (code "53") (name "Net-(R11-Pad2)") (class "Default")
      (node (ref "R11") (pin "2") (pinfunction "2_2") (pintype "passive"))
      (node (ref "R13") (pin "2") (pinfunction "2_2") (pintype "passive"))
      (node (ref "T3") (pin "C") (pinfunction "C_C") (pintype "passive"))
    )
    (net (code "54") (name "Net-(R21-Pad2)") (class "Default")
      (node (ref "R21") (pin "2") (pinfunction "2_2") (pintype "passive"))
      (node (ref "R23") (pin "2") (pinfunction "2_2") (pintype "passive"))
      (node (ref "T7") (pin "C") (pinfunction "C_C") (pintype "passive"))
    )
    (net (code "55") (name "Net-(R27-Pad2)") (class "Default")
      (node (ref "R27") (pin "2") (pinfunction "2_2") (pintype "passive"))
      (node (ref "T4") (pin "C") (pinfunction "C_C") (pintype "passive"))
    )
    (net (code "56") (name "Net-(R28-Pad2)") (class "Default")
      (node (ref "R28") (pin "2") (pinfunction "2_2") (pintype "passive"))
      (node (ref "R30") (pin "2") (pinfunction "2_2") (pintype "passive"))
      (node (ref "T3") (pin "B") (pinfunction "B_B") (pintype "passive"))
    )
    (net (code "57") (name "Net-(R29-Pad1)") (class "Default")
      (node (ref "R29") (pin "1") (pinfunction "1_1") (pintype "passive"))
      (node (ref "R53") (pin "2") (pinfunction "2_2") (pintype "passive"))
      (node (ref "T4") (pin "B") (pinfunction "B_B") (pintype "passive"))
    )
    (net (code "58") (name "Net-(R36-Pad2)") (class "Default")
      (node (ref "R36") (pin "2") (pinfunction "2_2") (pintype "passive"))
      (node (ref "T8") (pin "C") (pinfunction "C_C") (pintype "passive"))
    )
    (net (code "59") (name "Net-(R37-Pad2)") (class "Default")
      (node (ref "R37") (pin "2") (pinfunction "2_2") (pintype "passive"))
      (node (ref "R39") (pin "2") (pinfunction "2_2") (pintype "passive"))
      (node (ref "T7") (pin "B") (pinfunction "B_B") (pintype "passive"))
    )
    (net (code "60") (name "Net-(R38-Pad2)") (class "Default")
      (node (ref "R38") (pin "2") (pinfunction "2_2") (pintype "passive"))
      (node (ref "R54") (pin "2") (pinfunction "2_2") (pintype "passive"))
      (node (ref "T8") (pin "B") (pinfunction "B_B") (pintype "passive"))
    )
    (net (code "61") (name "Net-(T1-B)") (class "Default")
      (node (ref "R24") (pin "2") (pinfunction "2_2") (pintype "passive"))
      (node (ref "R25") (pin "1") (pinfunction "1_1") (pintype "passive"))
      (node (ref "T1") (pin "2") (pinfunction "B_2") (pintype "passive"))
    )
    (net (code "62") (name "Net-(T1-E)") (class "Default")
      (node (ref "R26") (pin "2") (pinfunction "2_2") (pintype "passive"))
      (node (ref "T1") (pin "1") (pinfunction "E_1") (pintype "passive"))
      (node (ref "T2") (pin "B") (pinfunction "B_B") (pintype "passive"))
    )
    (net (code "63") (name "Net-(T2-PadC)") (class "Default")
      (node (ref "T2") (pin "C") (pinfunction "C_C") (pintype "passive"))
      (node (ref "T3") (pin "E") (pinfunction "E_E") (pintype "passive"))
      (node (ref "T4") (pin "E") (pinfunction "E_E") (pintype "passive"))
    )
    (net (code "64") (name "Net-(T5-B)") (class "Default")
      (node (ref "R33") (pin "2") (pinfunction "2_2") (pintype "passive"))
      (node (ref "R34") (pin "1") (pinfunction "1_1") (pintype "passive"))
      (node (ref "T5") (pin "2") (pinfunction "B_2") (pintype "passive"))
    )
    (net (code "65") (name "Net-(T5-E)") (class "Default")
      (node (ref "R35") (pin "2") (pinfunction "2_2") (pintype "passive"))
      (node (ref "T5") (pin "1") (pinfunction "E_1") (pintype "passive"))
      (node (ref "T6") (pin "B") (pinfunction "B_B") (pintype "passive"))
    )
    (net (code "66") (name "Net-(T6-PadC)") (class "Default")
      (node (ref "T6") (pin "C") (pinfunction "C_C") (pintype "passive"))
      (node (ref "T7") (pin "E") (pinfunction "E_E") (pintype "passive"))
      (node (ref "T8") (pin "E") (pinfunction "E_E") (pintype "passive"))
    )
    (net (code "67") (name "Net-(VR1-E)") (class "Default")
      (node (ref "R14") (pin "1") (pinfunction "1_1") (pintype "passive"))
      (node (ref "VR1") (pin "3") (pinfunction "E_3") (pintype "passive"))
    )
    (net (code "68") (name "Net-(VR2-E)") (class "Default")
      (node (ref "R32") (pin "1") (pinfunction "1_1") (pintype "passive"))
      (node (ref "VR2") (pin "3") (pinfunction "E_3") (pintype "passive"))
    )
    (net (code "69") (name "Net-(VR4-S)") (class "Default")
      (node (ref "R33") (pin "1") (pinfunction "1_1") (pintype "passive"))
      (node (ref "VR4") (pin "2") (pinfunction "S_2") (pintype "passive"))
    )
    (net (code "70") (name "Net-(VR5-S)") (class "Default")
      (node (ref "R24") (pin "1") (pinfunction "1_1") (pintype "passive"))
      (node (ref "VR5") (pin "2") (pinfunction "S_2") (pintype "passive"))
    )
    (net (code "71") (name "OUTA") (class "Default")
      (node (ref "C7") (pin "2") (pinfunction "2_2") (pintype "passive"))
      (node (ref "U$5") (pin "P$1") (pinfunction "2_P$1") (pintype "passive"))
    )
    (net (code "72") (name "OUTAB") (class "Default")
      (node (ref "C12") (pin "2") (pinfunction "2_2") (pintype "passive"))
      (node (ref "U$9") (pin "P$1") (pinfunction "2_P$1") (pintype "passive"))
    )
    (net (code "73") (name "OUTB") (class "Default")
      (node (ref "C11") (pin "2") (pinfunction "2_2") (pintype "passive"))
      (node (ref "U$6") (pin "P$1") (pinfunction "2_P$1") (pintype "passive"))
    )
    (net (code "74") (name "unconnected-(OTA1A-BIAS-Pad2)") (class "Default")
      (node (ref "OTA1") (pin "2") (pinfunction "BIAS_2") (pintype "input"))
    )
    (net (code "75") (name "unconnected-(OTA1B-BIAS-Pad15)") (class "Default")
      (node (ref "OTA1") (pin "15") (pinfunction "BIAS_15") (pintype "input"))
    )
    (net (code "76") (name "unconnected-(OTA3A-BIAS-Pad2)") (class "Default")
      (node (ref "OTA3") (pin "2") (pinfunction "BIAS_2") (pintype "input"))
    )
    (net (code "77") (name "unconnected-(OTA3B-BIAS-Pad15)") (class "Default")
      (node (ref "OTA3") (pin "15") (pinfunction "BIAS_15") (pintype "input"))
    )
    (net (code "78") (name "unconnected-(POWER-Pad1)") (class "Default")
      (node (ref "POWER") (pin "1") (pinfunction "1_1") (pintype "passive"))
    )
    (net (code "79") (name "unconnected-(POWER-Pad2)") (class "Default")
      (node (ref "POWER") (pin "2") (pinfunction "2_2") (pintype "passive"))
    )
    (net (code "80") (name "unconnected-(POWER-Pad10)") (class "Default")
      (node (ref "POWER") (pin "10") (pinfunction "10_10") (pintype "passive"))
    )
    (net (code "81") (name "unconnected-(U$2-3-PadP$2)") (class "Default")
      (node (ref "U$2") (pin "P$2") (pinfunction "3_P$2") (pintype "passive"))
    )
    (net (code "82") (name "unconnected-(U$3-3-PadP$2)") (class "Default")
      (node (ref "U$3") (pin "P$2") (pinfunction "3_P$2") (pintype "passive"))
    )
    (net (code "83") (name "unconnected-(U$4-3-PadP$2)") (class "Default")
      (node (ref "U$4") (pin "P$2") (pinfunction "3_P$2") (pintype "passive"))
    )
    (net (code "84") (name "unconnected-(U$5-3-PadP$2)") (class "Default")
      (node (ref "U$5") (pin "P$2") (pinfunction "3_P$2") (pintype "passive"))
    )
    (net (code "85") (name "unconnected-(U$6-3-PadP$2)") (class "Default")
      (node (ref "U$6") (pin "P$2") (pinfunction "3_P$2") (pintype "passive"))
    )
    (net (code "86") (name "unconnected-(U$7-3-PadP$2)") (class "Default")
      (node (ref "U$7") (pin "P$2") (pinfunction "3_P$2") (pintype "passive"))
    )
    (net (code "87") (name "unconnected-(U$8-3-PadP$2)") (class "Default")
      (node (ref "U$8") (pin "P$2") (pinfunction "3_P$2") (pintype "passive"))
    )
    (net (code "88") (name "unconnected-(U$9-3-PadP$2)") (class "Default")
      (node (ref "U$9") (pin "P$2") (pinfunction "3_P$2") (pintype "passive"))
    )
    (net (code "89") (name "unconnected-(U$10-3-PadP$2)") (class "Default")
      (node (ref "U$10") (pin "P$2") (pinfunction "3_P$2") (pintype "passive"))
    )
    (net (code "90") (name "unconnected-(U$11-3-PadP$2)") (class "Default")
      (node (ref "U$11") (pin "P$2") (pinfunction "3_P$2") (pintype "passive"))
    )
  )
)
